# Exemplo_1.net
KiCad netlist of a schematic drawn in Altium Designer
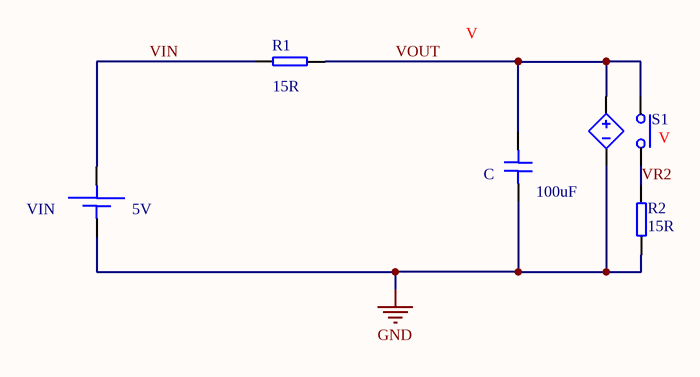
[diagram p0: Exemplo_1.SchDoc]

(export (version "E")
  (design (tool "Eeschema 10.0.6"))
  (components
    (comp (ref "C")
      (value "100uF")
      (description "CERAMIC CAPACITOR 10uF 50V 5% -55C TO 125C SMD 0805")
      (libsource (lib "Daagno") (part "CAP 10uF 50V SMD 0805"))
    )
    (comp (ref "R1")
      (value "15R")
      (description "CHIP RESISTOR 10K 1/8W 5% -55C TO 125C SMD 0805")
      (fields (field (name "Comment") "10K 1/8W"))
      (libsource (lib "Daagno") (part "RES 10K 1/8W SMD 0805"))
    )
    (comp (ref "R2")
      (value "15R")
      (description "CHIP RESISTOR 10K 1/8W 5% -55C TO 125C SMD 0805")
      (fields (field (name "Comment") "10K 1/8W"))
      (libsource (lib "Daagno") (part "RES 10K 1/8W SMD 0805"))
    )
    (comp (ref "S1")
      (value "VCSW")
      (description "GENERIC VOLTAGE CONTROLLED SWITCH FOR SIMULATION")
      (libsource (lib "Daagno") (part "VOLTAGE CONTROLLED SWITCH"))
    )
    (comp (ref "VIN")
      (value "5V")
      (description "GENERIC DC SOURCE FOR SIMULATION")
      (libsource (lib "Daagno") (part "DC SOURCE"))
    )
  )
  (nets
    (net (code "1") (name "/VIN") (class "Default")
      (node (ref "R1") (pin "1") (pinfunction "1_1") (pintype "passive"))
      (node (ref "VIN") (pin "1") (pinfunction "1_1") (pintype "passive"))
    )
    (net (code "2") (name "/VOUT") (class "Default")
      (node (ref "C") (pin "1") (pinfunction "1_1") (pintype "passive"))
      (node (ref "R1") (pin "2") (pinfunction "2_2") (pintype "passive"))
      (node (ref "S1") (pin "1") (pinfunction "1_1") (pintype "passive"))
      (node (ref "S1") (pin "3") (pinfunction "3_3") (pintype "passive"))
    )
    (net (code "3") (name "/VR2") (class "Default")
      (node (ref "R2") (pin "2") (pinfunction "2_2") (pintype "passive"))
      (node (ref "S1") (pin "4") (pinfunction "4_4") (pintype "passive"))
    )
    (net (code "4") (name "GND") (class "Default")
      (node (ref "C") (pin "2") (pinfunction "2_2") (pintype "passive"))
      (node (ref "R2") (pin "1") (pinfunction "1_1") (pintype "passive"))
      (node (ref "S1") (pin "2") (pinfunction "2_2") (pintype "passive"))
      (node (ref "VIN") (pin "2") (pinfunction "2_2") (pintype "passive"))
    )
  )
)
